# FLOLED.net
KiCad netlist of a schematic drawn in Altium Designer
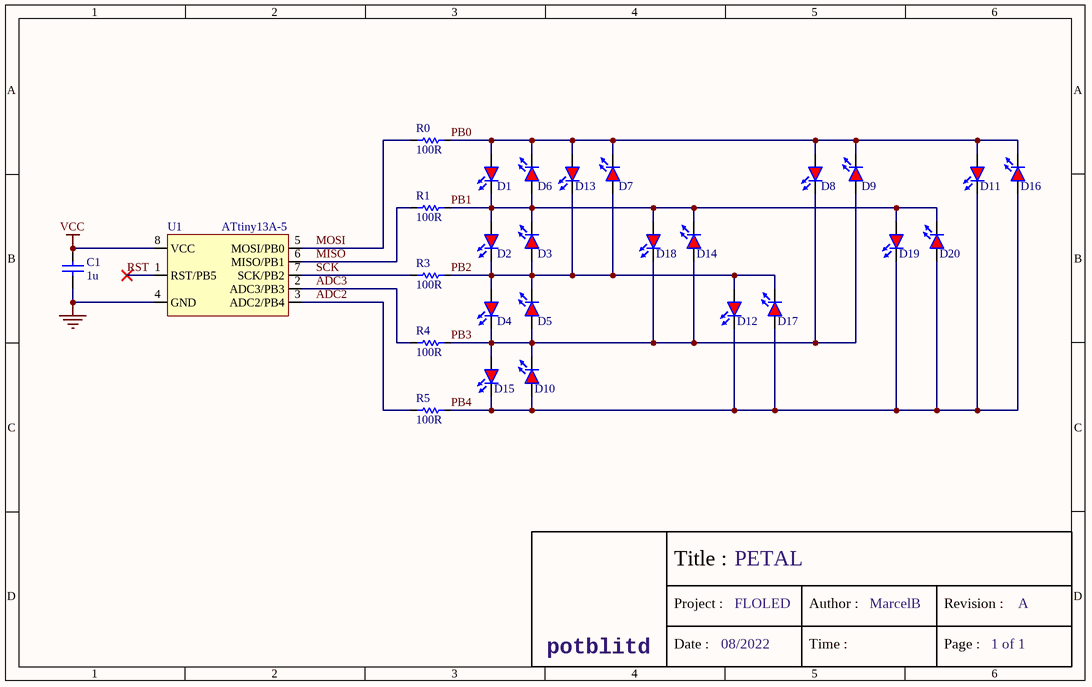
[diagram p0: FLOLED.SchDoc]

(export (version "E")
  (design (tool "Eeschema 10.0.6"))
  (components
    (comp (ref "C1")
      (value "Capacitor")
      (footprint "0603C")
      (description "Capacitor 1uF")
      (fields (field (name "ALTIUM_VALUE") "1u"))
      (libsource (lib "Simulation Generic Components") (part "Capacitor"))
    )
    (comp (ref "D1")
      (value "LED Red")
      (footprint "0805D")
      (description "Red LED Vf=2.1V Ic=20mA")
      (libsource (lib "AltiumLib") (part "LED-R"))
    )
    (comp (ref "D2")
      (value "LED Red")
      (footprint "0805D")
      (description "Red LED Vf=2.1V Ic=20mA")
      (libsource (lib "AltiumLib") (part "LED-R"))
    )
    (comp (ref "D3")
      (value "LED Red")
      (footprint "0805D")
      (description "Red LED Vf=2.1V Ic=20mA")
      (libsource (lib "AltiumLib") (part "LED-R"))
    )
    (comp (ref "D4")
      (value "LED Red")
      (footprint "0805D")
      (description "Red LED Vf=2.1V Ic=20mA")
      (libsource (lib "AltiumLib") (part "LED-R"))
    )
    (comp (ref "D5")
      (value "LED Red")
      (footprint "0805D")
      (description "Red LED Vf=2.1V Ic=20mA")
      (libsource (lib "AltiumLib") (part "LED-R"))
    )
    (comp (ref "D6")
      (value "LED Red")
      (footprint "0805D")
      (description "Red LED Vf=2.1V Ic=20mA")
      (libsource (lib "AltiumLib") (part "LED-R"))
    )
    (comp (ref "D7")
      (value "LED Red")
      (footprint "0805D")
      (description "Red LED Vf=2.1V Ic=20mA")
      (libsource (lib "AltiumLib") (part "LED-R"))
    )
    (comp (ref "D8")
      (value "LED Red")
      (footprint "0805D")
      (description "Red LED Vf=2.1V Ic=20mA")
      (libsource (lib "AltiumLib") (part "LED-R"))
    )
    (comp (ref "D9")
      (value "LED Red")
      (footprint "0805D")
      (description "Red LED Vf=2.1V Ic=20mA")
      (libsource (lib "AltiumLib") (part "LED-R"))
    )
    (comp (ref "D10")
      (value "LED Red")
      (footprint "0805D")
      (description "Red LED Vf=2.1V Ic=20mA")
      (libsource (lib "AltiumLib") (part "LED-R"))
    )
    (comp (ref "D11")
      (value "LED Red")
      (footprint "0805D")
      (description "Red LED Vf=2.1V Ic=20mA")
      (libsource (lib "AltiumLib") (part "LED-R"))
    )
    (comp (ref "D12")
      (value "LED Red")
      (footprint "0805D")
      (description "Red LED Vf=2.1V Ic=20mA")
      (libsource (lib "AltiumLib") (part "LED-R"))
    )
    (comp (ref "D13")
      (value "LED Red")
      (footprint "0805D")
      (description "Red LED Vf=2.1V Ic=20mA")
      (libsource (lib "AltiumLib") (part "LED-R"))
    )
    (comp (ref "D14")
      (value "LED Red")
      (footprint "0805D")
      (description "Red LED Vf=2.1V Ic=20mA")
      (libsource (lib "AltiumLib") (part "LED-R"))
    )
    (comp (ref "D15")
      (value "LED Red")
      (footprint "0805D")
      (description "Red LED Vf=2.1V Ic=20mA")
      (libsource (lib "AltiumLib") (part "LED-R"))
    )
    (comp (ref "D16")
      (value "LED Red")
      (footprint "0805D")
      (description "Red LED Vf=2.1V Ic=20mA")
      (libsource (lib "AltiumLib") (part "LED-R"))
    )
    (comp (ref "D17")
      (value "LED Red")
      (footprint "0805D")
      (description "Red LED Vf=2.1V Ic=20mA")
      (libsource (lib "AltiumLib") (part "LED-R"))
    )
    (comp (ref "D18")
      (value "LED Red")
      (footprint "0805D")
      (description "Red LED Vf=2.1V Ic=20mA")
      (libsource (lib "AltiumLib") (part "LED-R"))
    )
    (comp (ref "D19")
      (value "LED Red")
      (footprint "0805D")
      (description "Red LED Vf=2.1V Ic=20mA")
      (libsource (lib "AltiumLib") (part "LED-R"))
    )
    (comp (ref "D20")
      (value "LED Red")
      (footprint "0805D")
      (description "Red LED Vf=2.1V Ic=20mA")
      (libsource (lib "AltiumLib") (part "LED-R"))
    )
    (comp (ref "R0")
      (value "100R")
      (footprint "0805R")
      (description "Resistor 100Ω")
      (fields (field (name "Comment") "Resistor"))
      (libsource (lib "AltiumLib") (part "RES"))
    )
    (comp (ref "R1")
      (value "100R")
      (footprint "0805R")
      (description "Resistor 100Ω")
      (fields (field (name "Comment") "Resistor"))
      (libsource (lib "AltiumLib") (part "RES"))
    )
    (comp (ref "R3")
      (value "100R")
      (footprint "0805R")
      (description "Resistor 100Ω")
      (fields (field (name "Comment") "Resistor"))
      (libsource (lib "AltiumLib") (part "RES"))
    )
    (comp (ref "R4")
      (value "100R")
      (footprint "0805R")
      (description "Resistor 100Ω")
      (fields (field (name "Comment") "Resistor"))
      (libsource (lib "AltiumLib") (part "RES"))
    )
    (comp (ref "R5")
      (value "100R")
      (footprint "0805R")
      (description "Resistor 100Ω")
      (fields (field (name "Comment") "Resistor"))
      (libsource (lib "AltiumLib") (part "RES"))
    )
    (comp (ref "U1")
      (value "ATtiny13A-5")
      (footprint "DIP-8 - SMD")
      (description "tiny AVR 8-pin microcontroller")
      (libsource (lib "AltiumLib") (part "ATtiny13A-5"))
    )
  )
  (nets
    (net (code "1") (name "/ADC2") (class "Default")
      (node (ref "R5") (pin "1") (pinfunction "1_1") (pintype "passive"))
      (node (ref "U1") (pin "3") (pinfunction "ADC2/PB4_3") (pintype "passive"))
    )
    (net (code "2") (name "/ADC3") (class "Default")
      (node (ref "R4") (pin "1") (pinfunction "1_1") (pintype "passive"))
      (node (ref "U1") (pin "2") (pinfunction "ADC3/PB3_2") (pintype "passive"))
    )
    (net (code "3") (name "/MISO") (class "Default")
      (node (ref "R1") (pin "1") (pinfunction "1_1") (pintype "passive"))
      (node (ref "U1") (pin "6") (pinfunction "MISO/PB1_6") (pintype "passive"))
    )
    (net (code "4") (name "/MOSI") (class "Default")
      (node (ref "R0") (pin "1") (pinfunction "1_1") (pintype "passive"))
      (node (ref "U1") (pin "5") (pinfunction "MOSI/PB0_5") (pintype "passive"))
    )
    (net (code "5") (name "/PB0") (class "Default")
      (node (ref "D1") (pin "1") (pintype "passive"))
      (node (ref "D11") (pin "1") (pintype "passive"))
      (node (ref "D13") (pin "1") (pintype "passive"))
      (node (ref "D16") (pin "2") (pintype "passive"))
      (node (ref "D6") (pin "2") (pintype "passive"))
      (node (ref "D7") (pin "2") (pintype "passive"))
      (node (ref "D8") (pin "1") (pintype "passive"))
      (node (ref "D9") (pin "2") (pintype "passive"))
      (node (ref "R0") (pin "2") (pinfunction "2_2") (pintype "passive"))
    )
    (net (code "6") (name "/PB1") (class "Default")
      (node (ref "D1") (pin "2") (pintype "passive"))
      (node (ref "D14") (pin "2") (pintype "passive"))
      (node (ref "D18") (pin "1") (pintype "passive"))
      (node (ref "D19") (pin "1") (pintype "passive"))
      (node (ref "D2") (pin "1") (pintype "passive"))
      (node (ref "D20") (pin "2") (pintype "passive"))
      (node (ref "D3") (pin "2") (pintype "passive"))
      (node (ref "D6") (pin "1") (pintype "passive"))
      (node (ref "R1") (pin "2") (pinfunction "2_2") (pintype "passive"))
    )
    (net (code "7") (name "/PB2") (class "Default")
      (node (ref "D12") (pin "1") (pintype "passive"))
      (node (ref "D13") (pin "2") (pintype "passive"))
      (node (ref "D17") (pin "2") (pintype "passive"))
      (node (ref "D2") (pin "2") (pintype "passive"))
      (node (ref "D3") (pin "1") (pintype "passive"))
      (node (ref "D4") (pin "1") (pintype "passive"))
      (node (ref "D5") (pin "2") (pintype "passive"))
      (node (ref "D7") (pin "1") (pintype "passive"))
      (node (ref "R3") (pin "2") (pinfunction "2_2") (pintype "passive"))
    )
    (net (code "8") (name "/PB3") (class "Default")
      (node (ref "D10") (pin "2") (pintype "passive"))
      (node (ref "D14") (pin "1") (pintype "passive"))
      (node (ref "D15") (pin "1") (pintype "passive"))
      (node (ref "D18") (pin "2") (pintype "passive"))
      (node (ref "D4") (pin "2") (pintype "passive"))
      (node (ref "D5") (pin "1") (pintype "passive"))
      (node (ref "D8") (pin "2") (pintype "passive"))
      (node (ref "D9") (pin "1") (pintype "passive"))
      (node (ref "R4") (pin "2") (pinfunction "2_2") (pintype "passive"))
    )
    (net (code "9") (name "/PB4") (class "Default")
      (node (ref "D10") (pin "1") (pintype "passive"))
      (node (ref "D11") (pin "2") (pintype "passive"))
      (node (ref "D12") (pin "2") (pintype "passive"))
      (node (ref "D15") (pin "2") (pintype "passive"))
      (node (ref "D16") (pin "1") (pintype "passive"))
      (node (ref "D17") (pin "1") (pintype "passive"))
      (node (ref "D19") (pin "2") (pintype "passive"))
      (node (ref "D20") (pin "1") (pintype "passive"))
      (node (ref "R5") (pin "2") (pinfunction "2_2") (pintype "passive"))
    )
    (net (code "10") (name "/RST") (class "Default")
      (node (ref "U1") (pin "1") (pinfunction "RST/PB5_1") (pintype "passive+no_connect"))
    )
    (net (code "11") (name "/SCK") (class "Default")
      (node (ref "R3") (pin "1") (pinfunction "1_1") (pintype "passive"))
      (node (ref "U1") (pin "7") (pinfunction "SCK/PB2_7") (pintype "passive"))
    )
    (net (code "12") (name "GND") (class "Default")
      (node (ref "C1") (pin "1") (pinfunction "1_1") (pintype "passive"))
      (node (ref "U1") (pin "4") (pinfunction "GND_4") (pintype "passive"))
    )
    (net (code "13") (name "VCC") (class "Default")
      (node (ref "C1") (pin "2") (pinfunction "2_2") (pintype "passive"))
      (node (ref "U1") (pin "8") (pinfunction "VCC_8") (pintype "passive"))
    )
  )
)
